# ArduTester.net
KiCad netlist of a schematic drawn in EAGLE
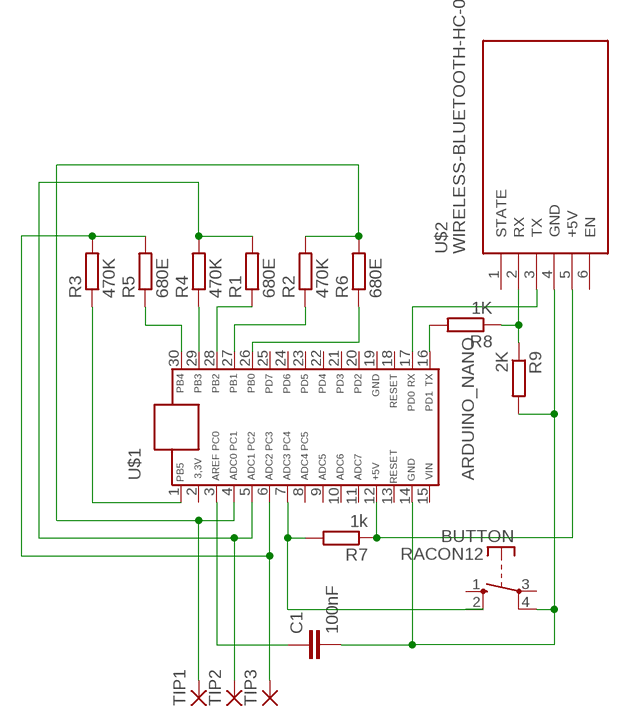
[diagram p0: schematic, sheet 1]

(export (version "E")
  (design (tool "Eeschema 10.0.6"))
  (components
    (comp (ref "BUTTON")
      (value "RACON12")
      (footprint "eagle-import:RACON12")
      (libsource (lib "eagle-import") (part "RACON12"))
    )
    (comp (ref "C1")
      (value "100nF")
      (footprint "eagle-import:C050-024X044")
      (libsource (lib "eagle-import") (part "C-EU050-024X044"))
    )
    (comp (ref "R1")
      (value "680E")
      (footprint "eagle-import:0204_7")
      (libsource (lib "eagle-import") (part "R-EU_0204/7"))
    )
    (comp (ref "R2")
      (value "470K")
      (footprint "eagle-import:0204_7")
      (libsource (lib "eagle-import") (part "R-EU_0204/7"))
    )
    (comp (ref "R3")
      (value "470K")
      (footprint "eagle-import:0204_7")
      (libsource (lib "eagle-import") (part "R-EU_0204/7"))
    )
    (comp (ref "R4")
      (value "470K")
      (footprint "eagle-import:0204_7")
      (libsource (lib "eagle-import") (part "R-EU_0204/7"))
    )
    (comp (ref "R5")
      (value "680E")
      (footprint "eagle-import:0204_7")
      (libsource (lib "eagle-import") (part "R-EU_0204/7"))
    )
    (comp (ref "R6")
      (value "680E")
      (footprint "eagle-import:0204_7")
      (libsource (lib "eagle-import") (part "R-EU_0204/7"))
    )
    (comp (ref "R7")
      (value "1k")
      (footprint "eagle-import:0204_7")
      (libsource (lib "eagle-import") (part "R-EU_0204/7"))
    )
    (comp (ref "R8")
      (value "1K")
      (footprint "eagle-import:0204_7")
      (libsource (lib "eagle-import") (part "R-EU_0204/7"))
    )
    (comp (ref "R9")
      (value "2K")
      (footprint "eagle-import:0204_7")
      (libsource (lib "eagle-import") (part "R-EU_0204/7"))
    )
    (comp (ref "TIP1")
      (value "2,54/0,9")
      (footprint "eagle-import:2,54_0,9")
      (libsource (lib "eagle-import") (part "2,54/0,9"))
    )
    (comp (ref "TIP2")
      (value "2,54/0,9")
      (footprint "eagle-import:2,54_0,9")
      (libsource (lib "eagle-import") (part "2,54/0,9"))
    )
    (comp (ref "TIP3")
      (value "2,54/0,9")
      (footprint "eagle-import:2,54_0,9")
      (libsource (lib "eagle-import") (part "2,54/0,9"))
    )
    (comp (ref "U$1")
      (value "ARDUINO_NANO")
      (footprint "eagle-import:ARDUINO_NANO")
      (libsource (lib "eagle-import") (part "ARDUINO_NANO"))
    )
    (comp (ref "U$2")
      (value "WIRELESS-BLUETOOTH-HC-05")
      (footprint "eagle-import:WIRELESS-BLUETOOTH-HC-05")
      (libsource (lib "eagle-import") (part "WIRELESS-BLUETOOTH-HC-05"))
    )
  )
  (nets
    (net (code "1") (name "Net-(BUTTON-S-Pad2)") (class "Default")
      (node (ref "BUTTON") (pin "2") (pinfunction "S_2") (pintype "passive"))
      (node (ref "R7") (pin "2") (pinfunction "2_2") (pintype "passive"))
      (node (ref "U$1") (pin "7") (pinfunction "7_7") (pintype "passive"))
    )
    (net (code "2") (name "Net-(C1-Pad1)") (class "Default")
      (node (ref "C1") (pin "1") (pinfunction "1_1") (pintype "passive"))
      (node (ref "U$1") (pin "3") (pinfunction "3_3") (pintype "passive"))
    )
    (net (code "3") (name "Net-(R1-Pad1)") (class "Default")
      (node (ref "R1") (pin "1") (pinfunction "1_1") (pintype "passive"))
      (node (ref "U$1") (pin "28") (pinfunction "28_28") (pintype "passive"))
    )
    (net (code "4") (name "Net-(R2-Pad1)") (class "Default")
      (node (ref "R2") (pin "1") (pinfunction "1_1") (pintype "passive"))
      (node (ref "U$1") (pin "27") (pinfunction "27_27") (pintype "passive"))
    )
    (net (code "5") (name "Net-(R3-Pad1)") (class "Default")
      (node (ref "R3") (pin "1") (pinfunction "1_1") (pintype "passive"))
      (node (ref "U$1") (pin "1") (pinfunction "1_1") (pintype "passive"))
    )
    (net (code "6") (name "Net-(R4-Pad1)") (class "Default")
      (node (ref "R4") (pin "1") (pinfunction "1_1") (pintype "passive"))
      (node (ref "U$1") (pin "29") (pinfunction "29_29") (pintype "passive"))
    )
    (net (code "7") (name "Net-(R5-Pad1)") (class "Default")
      (node (ref "R5") (pin "1") (pinfunction "1_1") (pintype "passive"))
      (node (ref "U$1") (pin "30") (pinfunction "30_30") (pintype "passive"))
    )
    (net (code "8") (name "Net-(R6-Pad1)") (class "Default")
      (node (ref "R6") (pin "1") (pinfunction "1_1") (pintype "passive"))
      (node (ref "U$1") (pin "26") (pinfunction "26_26") (pintype "passive"))
    )
    (net (code "9") (name "Net-(R8-Pad2)") (class "Default")
      (node (ref "R8") (pin "2") (pinfunction "2_2") (pintype "passive"))
      (node (ref "U$1") (pin "16") (pinfunction "16_16") (pintype "passive"))
    )
    (net (code "10") (name "Net-(TIP1-P)") (class "Default")
      (node (ref "R2") (pin "2") (pinfunction "2_2") (pintype "passive"))
      (node (ref "R6") (pin "2") (pinfunction "2_2") (pintype "passive"))
      (node (ref "TIP1") (pin "1") (pinfunction "P_1") (pintype "passive"))
      (node (ref "U$1") (pin "4") (pinfunction "4_4") (pintype "passive"))
    )
    (net (code "11") (name "Net-(TIP2-P)") (class "Default")
      (node (ref "R1") (pin "2") (pinfunction "2_2") (pintype "passive"))
      (node (ref "R4") (pin "2") (pinfunction "2_2") (pintype "passive"))
      (node (ref "TIP2") (pin "1") (pinfunction "P_1") (pintype "passive"))
      (node (ref "U$1") (pin "5") (pinfunction "5_5") (pintype "passive"))
    )
    (net (code "12") (name "Net-(TIP3-P)") (class "Default")
      (node (ref "R3") (pin "2") (pinfunction "2_2") (pintype "passive"))
      (node (ref "R5") (pin "2") (pinfunction "2_2") (pintype "passive"))
      (node (ref "TIP3") (pin "1") (pinfunction "P_1") (pintype "passive"))
      (node (ref "U$1") (pin "6") (pinfunction "6_6") (pintype "passive"))
    )
    (net (code "13") (name "Net-(U$2-+5V)") (class "Default")
      (node (ref "R7") (pin "1") (pinfunction "1_1") (pintype "passive"))
      (node (ref "U$1") (pin "12") (pinfunction "12_12") (pintype "passive"))
      (node (ref "U$2") (pin "5") (pinfunction "+5V_5") (pintype "power_in"))
    )
    (net (code "14") (name "Net-(U$2-GND)") (class "Default")
      (node (ref "BUTTON") (pin "4") (pinfunction "P_4") (pintype "passive"))
      (node (ref "C1") (pin "2") (pinfunction "2_2") (pintype "passive"))
      (node (ref "R9") (pin "2") (pinfunction "2_2") (pintype "passive"))
      (node (ref "U$1") (pin "14") (pinfunction "14_14") (pintype "passive"))
      (node (ref "U$2") (pin "4") (pinfunction "GND_4") (pintype "power_in"))
    )
    (net (code "15") (name "Net-(U$2-RX)") (class "Default")
      (node (ref "R8") (pin "1") (pinfunction "1_1") (pintype "passive"))
      (node (ref "R9") (pin "1") (pinfunction "1_1") (pintype "passive"))
      (node (ref "U$2") (pin "2") (pinfunction "RX_2") (pintype "bidirectional"))
    )
    (net (code "16") (name "Net-(U$2-TX)") (class "Default")
      (node (ref "U$1") (pin "17") (pinfunction "17_17") (pintype "passive"))
      (node (ref "U$2") (pin "3") (pinfunction "TX_3") (pintype "bidirectional"))
    )
    (net (code "17") (name "unconnected-(BUTTON-P-Pad3)") (class "Default")
      (node (ref "BUTTON") (pin "3") (pinfunction "P_3") (pintype "passive"))
    )
    (net (code "18") (name "unconnected-(BUTTON-S-Pad1)") (class "Default")
      (node (ref "BUTTON") (pin "1") (pinfunction "S_1") (pintype "passive"))
    )
    (net (code "19") (name "unconnected-(U$1-Pad2)") (class "Default")
      (node (ref "U$1") (pin "2") (pinfunction "2_2") (pintype "passive"))
    )
    (net (code "20") (name "unconnected-(U$1-Pad8)") (class "Default")
      (node (ref "U$1") (pin "8") (pinfunction "8_8") (pintype "passive"))
    )
    (net (code "21") (name "unconnected-(U$1-Pad9)") (class "Default")
      (node (ref "U$1") (pin "9") (pinfunction "9_9") (pintype "passive"))
    )
    (net (code "22") (name "unconnected-(U$1-Pad10)") (class "Default")
      (node (ref "U$1") (pin "10") (pinfunction "10_10") (pintype "passive"))
    )
    (net (code "23") (name "unconnected-(U$1-Pad11)") (class "Default")
      (node (ref "U$1") (pin "11") (pinfunction "11_11") (pintype "passive"))
    )
    (net (code "24") (name "unconnected-(U$1-Pad13)") (class "Default")
      (node (ref "U$1") (pin "13") (pinfunction "13_13") (pintype "passive"))
    )
    (net (code "25") (name "unconnected-(U$1-Pad15)") (class "Default")
      (node (ref "U$1") (pin "15") (pinfunction "15_15") (pintype "passive"))
    )
    (net (code "26") (name "unconnected-(U$1-Pad18)") (class "Default")
      (node (ref "U$1") (pin "18") (pinfunction "18_18") (pintype "passive"))
    )
    (net (code "27") (name "unconnected-(U$1-Pad19)") (class "Default")
      (node (ref "U$1") (pin "19") (pinfunction "19_19") (pintype "passive"))
    )
    (net (code "28") (name "unconnected-(U$1-Pad20)") (class "Default")
      (node (ref "U$1") (pin "20") (pinfunction "20_20") (pintype "passive"))
    )
    (net (code "29") (name "unconnected-(U$1-Pad21)") (class "Default")
      (node (ref "U$1") (pin "21") (pinfunction "21_21") (pintype "passive"))
    )
    (net (code "30") (name "unconnected-(U$1-Pad22)") (class "Default")
      (node (ref "U$1") (pin "22") (pinfunction "22_22") (pintype "passive"))
    )
    (net (code "31") (name "unconnected-(U$1-Pad23)") (class "Default")
      (node (ref "U$1") (pin "23") (pinfunction "23_23") (pintype "passive"))
    )
    (net (code "32") (name "unconnected-(U$1-Pad24)") (class "Default")
      (node (ref "U$1") (pin "24") (pinfunction "24_24") (pintype "passive"))
    )
    (net (code "33") (name "unconnected-(U$1-Pad25)") (class "Default")
      (node (ref "U$1") (pin "25") (pinfunction "25_25") (pintype "passive"))
    )
    (net (code "34") (name "unconnected-(U$2-EN-Pad6)") (class "Default")
      (node (ref "U$2") (pin "6") (pinfunction "EN_6") (pintype "bidirectional"))
    )
    (net (code "35") (name "unconnected-(U$2-STATE-Pad1)") (class "Default")
      (node (ref "U$2") (pin "1") (pinfunction "STATE_1") (pintype "bidirectional"))
    )
  )
)
